# POWER.net
KiCad netlist of a schematic drawn in Altium Designer
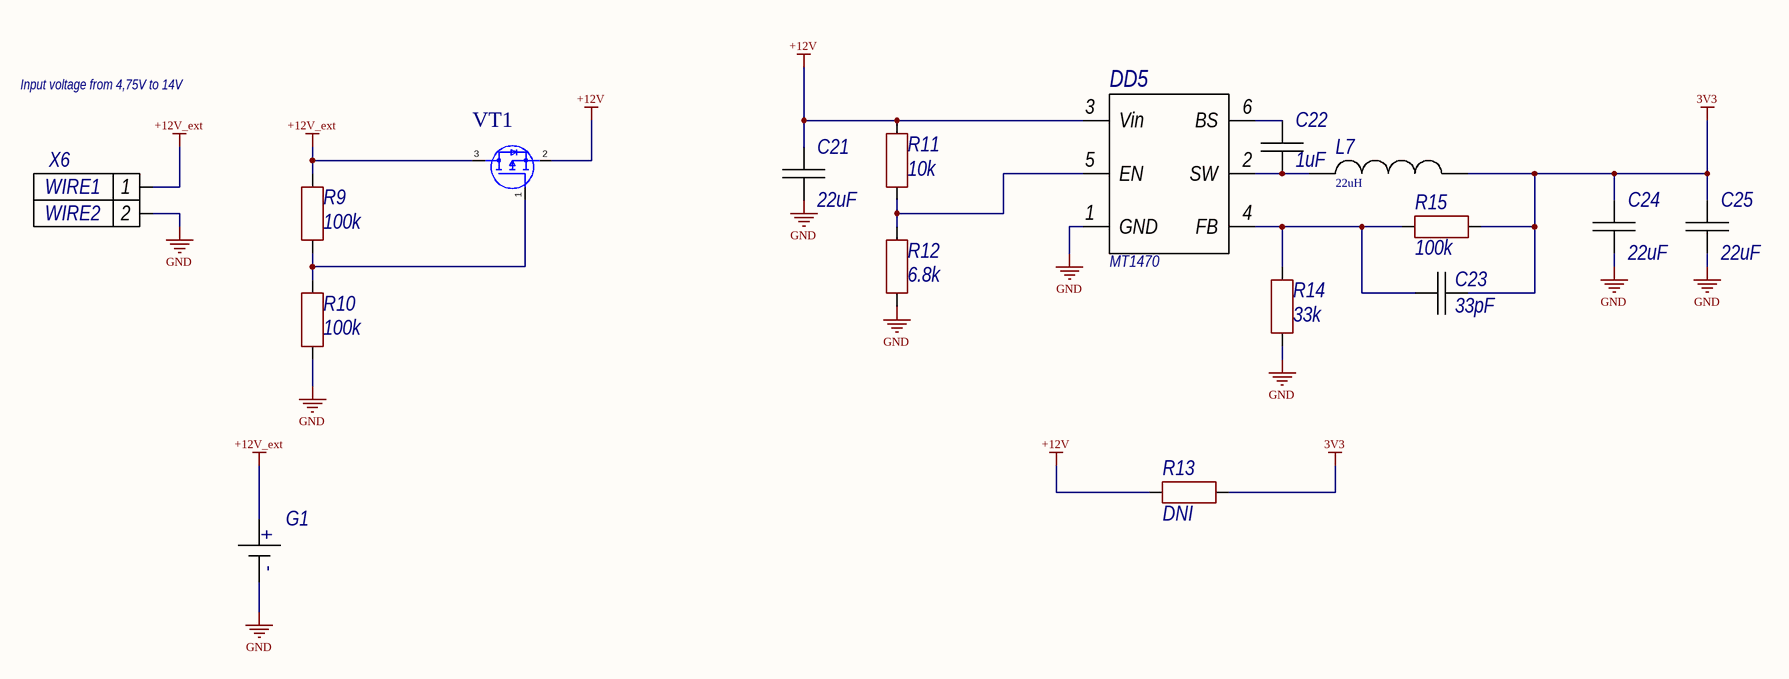
[diagram p0: POWER.SchDoc]

(export (version "E")
  (design (tool "Eeschema 10.0.6"))
  (components
    (comp (ref "C21")
      (value "22uF")
      (footprint "CAPC0805N")
      (fields (field (name "VOLTAGE") "25V") (field (name "PART NUMBER") "CAPC0805"))
      (libsource (lib "Library") (part "CAPC0805"))
    )
    (comp (ref "C22")
      (value "1uF")
      (footprint "CAPC0603N")
      (fields (field (name "PART NUMBER") "CAPC") (field (name "Comment") "1uF "))
      (libsource (lib "Library") (part "CAPC"))
    )
    (comp (ref "C23")
      (value "33pF")
      (footprint "CAP0402")
      (fields (field (name "PART NUMBER") "CAP0402") (field (name "Comment") "33pF "))
      (libsource (lib "Library") (part "CAPC"))
    )
    (comp (ref "C24")
      (value "22uF")
      (footprint "CAPC0805N")
      (fields (field (name "VOLTAGE") "25V") (field (name "PART NUMBER") "CAPC0805"))
      (libsource (lib "Library") (part "CAPC0805"))
    )
    (comp (ref "C25")
      (value "22uF")
      (footprint "CAPC0805N")
      (fields (field (name "VOLTAGE") "25V") (field (name "PART NUMBER") "CAPC0805"))
      (libsource (lib "Library") (part "CAPC0805"))
    )
    (comp (ref "DD5")
      (value "~")
      (footprint "SOT23-6")
      (fields
        (field (name "MPN") "MT1470")
        (field (name "PART NUMBER") "MT1470")
        (field (name "MANUFACTURER") "XI'AN Aerosemi Tech")
      )
      (libsource (lib "Library") (part "DD_MT1470"))
    )
    (comp (ref "G1")
      (value "C70373")
      (footprint "BAT-SMD_CR2032-3V")
      (libsource (lib "Library") (part "Battery"))
    )
    (comp (ref "L7")
      (value "22uH")
      (footprint "CAPC0805N")
      (fields (field (name "MANUFACTURER") "microgate") (field (name "MPN") "MGFL2012F220MT-LF"))
      (libsource (lib "Library") (part "Inductor"))
    )
    (comp (ref "R9")
      (value "100k")
      (footprint "RESC0402(1005)_M")
      (fields (field (name "PART NUMBER") "RES0402") (field (name "Comment") "100k "))
      (libsource (lib "Library") (part "RES"))
    )
    (comp (ref "R10")
      (value "100k")
      (footprint "RESC0402(1005)_M")
      (fields (field (name "PART NUMBER") "RES0402") (field (name "Comment") "100k "))
      (libsource (lib "Library") (part "RES"))
    )
    (comp (ref "R11")
      (value "10k")
      (footprint "RESC0402(1005)_M")
      (fields (field (name "PART NUMBER") "RES0402") (field (name "Comment") "10k "))
      (libsource (lib "Library") (part "RES"))
    )
    (comp (ref "R12")
      (value "6.8k")
      (footprint "RESC0402(1005)_M")
      (fields (field (name "PART NUMBER") "RES0402") (field (name "Comment") "6.8k "))
      (libsource (lib "Library") (part "RES"))
    )
    (comp (ref "R13")
      (value "DNI")
      (footprint "RESC0603N")
      (fields (field (name "PART NUMBER") "RES") (field (name "Comment") "DNI "))
      (libsource (lib "") (part "RES_1"))
    )
    (comp (ref "R14")
      (value "33k")
      (footprint "RESC0402(1005)_M")
      (fields (field (name "PART NUMBER") "RES0402") (field (name "Comment") "33k "))
      (libsource (lib "Library") (part "RES"))
    )
    (comp (ref "R15")
      (value "100k")
      (footprint "RESC0402(1005)_M")
      (fields (field (name "PART NUMBER") "RES0402") (field (name "Comment") "100k "))
      (libsource (lib "") (part "RES_1"))
    )
    (comp (ref "VT1")
      (value "AO3401A")
      (footprint "SOT-23")
      (libsource (lib "Library") (part "IRLML6401TRPBF"))
    )
    (comp (ref "X6")
      (value "DG500-5.0-02P-14")
      (footprint "DG500-5.0-02P-14")
      (fields (field (name "WIRE2") "WIRE2") (field (name "WIRE1") "WIRE1"))
      (libsource (lib "Library") (part "Connector_2pin"))
    )
  )
  (nets
    (net (code "1") (name "+12V") (class "Default")
      (node (ref "C21") (pin "2") (pinfunction "2_2") (pintype "passive"))
      (node (ref "DD5") (pin "3") (pinfunction "Vin_3") (pintype "passive"))
      (node (ref "R11") (pin "1") (pinfunction "1_1") (pintype "passive"))
      (node (ref "R13") (pin "1") (pinfunction "1_1") (pintype "passive"))
      (node (ref "VT1") (pin "2") (pinfunction "S_2") (pintype "passive"))
    )
    (net (code "2") (name "+12V_ext") (class "Default")
      (node (ref "G1") (pin "1") (pinfunction "+_1") (pintype "passive"))
      (node (ref "R9") (pin "1") (pinfunction "1_1") (pintype "passive"))
      (node (ref "VT1") (pin "3") (pinfunction "D_3") (pintype "passive"))
      (node (ref "X6") (pin "1") (pinfunction "1_1") (pintype "passive"))
    )
    (net (code "3") (name "3V3") (class "Default")
      (node (ref "C23") (pin "1") (pinfunction "1_1") (pintype "passive"))
      (node (ref "C24") (pin "2") (pinfunction "2_2") (pintype "passive"))
      (node (ref "C25") (pin "2") (pinfunction "2_2") (pintype "passive"))
      (node (ref "L7") (pin "2") (pinfunction "2_2") (pintype "passive"))
      (node (ref "R13") (pin "2") (pinfunction "2_2") (pintype "passive"))
      (node (ref "R15") (pin "2") (pinfunction "2_2") (pintype "passive"))
    )
    (net (code "4") (name "GND") (class "Default")
      (node (ref "C21") (pin "1") (pinfunction "1_1") (pintype "passive"))
      (node (ref "C24") (pin "1") (pinfunction "1_1") (pintype "passive"))
      (node (ref "C25") (pin "1") (pinfunction "1_1") (pintype "passive"))
      (node (ref "DD5") (pin "1") (pinfunction "GND_1") (pintype "passive"))
      (node (ref "G1") (pin "2") (pinfunction "-_2") (pintype "passive"))
      (node (ref "R10") (pin "2") (pinfunction "2_2") (pintype "passive"))
      (node (ref "R12") (pin "2") (pinfunction "2_2") (pintype "passive"))
      (node (ref "R14") (pin "2") (pinfunction "2_2") (pintype "passive"))
      (node (ref "X6") (pin "2") (pinfunction "2_2") (pintype "passive"))
    )
    (net (code "5") (name "Net-(DD5-BS)") (class "Default")
      (node (ref "C22") (pin "2") (pinfunction "2_2") (pintype "passive"))
      (node (ref "DD5") (pin "6") (pinfunction "BS_6") (pintype "passive"))
    )
    (net (code "6") (name "Net-(DD5-EN)") (class "Default")
      (node (ref "DD5") (pin "5") (pinfunction "EN_5") (pintype "passive"))
      (node (ref "R11") (pin "2") (pinfunction "2_2") (pintype "passive"))
      (node (ref "R12") (pin "1") (pinfunction "1_1") (pintype "passive"))
    )
    (net (code "7") (name "Net-(DD5-FB)") (class "Default")
      (node (ref "C23") (pin "2") (pinfunction "2_2") (pintype "passive"))
      (node (ref "DD5") (pin "4") (pinfunction "FB_4") (pintype "passive"))
      (node (ref "R14") (pin "1") (pinfunction "1_1") (pintype "passive"))
      (node (ref "R15") (pin "1") (pinfunction "1_1") (pintype "passive"))
    )
    (net (code "8") (name "Net-(DD5-SW)") (class "Default")
      (node (ref "C22") (pin "1") (pinfunction "1_1") (pintype "passive"))
      (node (ref "DD5") (pin "2") (pinfunction "SW_2") (pintype "passive"))
      (node (ref "L7") (pin "1") (pinfunction "1_1") (pintype "passive"))
    )
    (net (code "9") (name "Net-(VT1-G)") (class "Default")
      (node (ref "R10") (pin "1") (pinfunction "1_1") (pintype "passive"))
      (node (ref "R9") (pin "2") (pinfunction "2_2") (pintype "passive"))
      (node (ref "VT1") (pin "1") (pinfunction "G_1") (pintype "passive"))
    )
  )
)
